# eagleproject.net
KiCad netlist of a schematic drawn in EAGLE
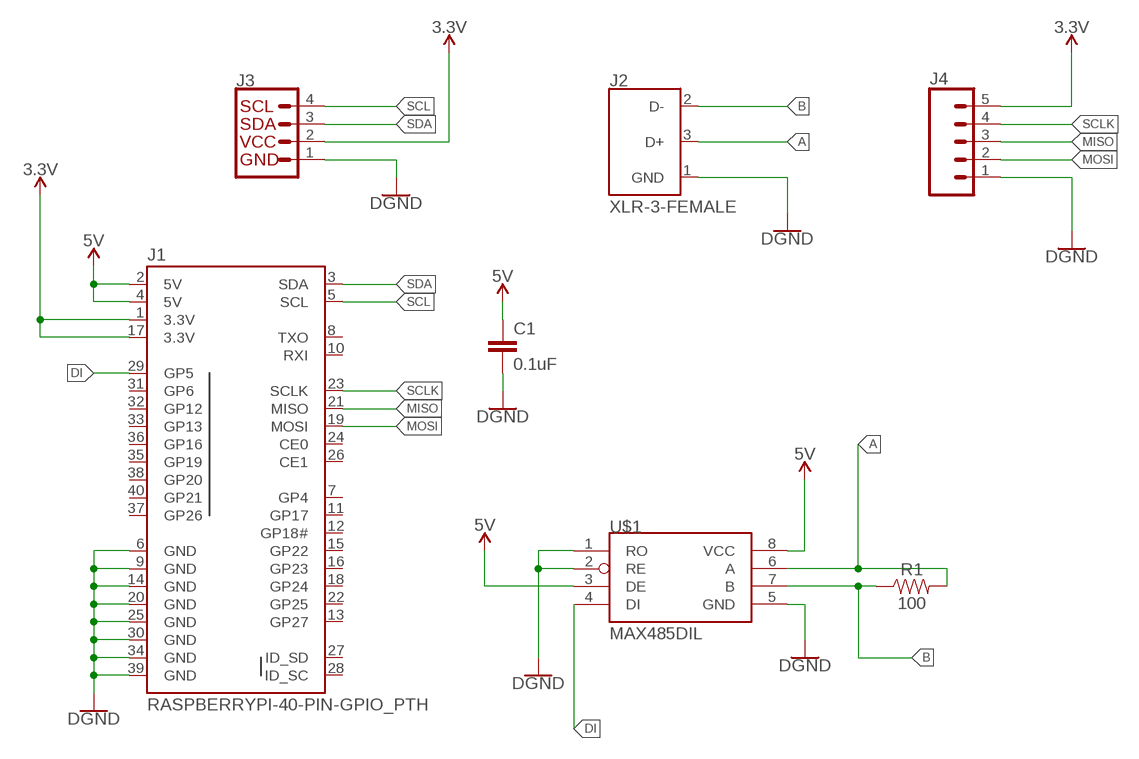
[diagram p0: schematic, sheet 1]

(export (version "E")
  (design (tool "Eeschema 10.0.6"))
  (components
    (comp (ref "C1")
      (value "0.1uF")
      (footprint "eagle-import:0603")
      (libsource (lib "eagle-import") (part "0.1UF-0603-25V-(+80/-20%)"))
    )
    (comp (ref "J1")
      (value "RASPBERRYPI-40-PIN-GPIO_PTH")
      (footprint "eagle-import:2X20_SHROUDED")
      (libsource (lib "eagle-import") (part "RASPBERRYPI-40-PIN-GPIO_PTH"))
    )
    (comp (ref "J2")
      (value "XLR-3-FEMALE")
      (footprint "eagle-import:XLR-3_FEMALE")
      (libsource (lib "eagle-import") (part "XLR-3-FEMALE"))
    )
    (comp (ref "J3")
      (value "I2C_STANDARD")
      (footprint "eagle-import:1X04")
      (libsource (lib "eagle-import") (part "I2C_STANDARD"))
    )
    (comp (ref "J4")
      (value "CONN_05")
      (footprint "eagle-import:1X05")
      (libsource (lib "eagle-import") (part "CONN_05"))
    )
    (comp (ref "R1")
      (value "100")
      (footprint "eagle-import:0603")
      (libsource (lib "eagle-import") (part "100OHM-0603-1/4W-5%"))
    )
    (comp (ref "U$1")
      (value "MAX485DIL")
      (footprint "eagle-import:DIL08")
      (libsource (lib "eagle-import") (part "MAX485DIL"))
    )
  )
  (nets
    (net (code "1") (name "3.3V") (class "Default")
      (node (ref "J1") (pin "1") (pinfunction "3.3V_1") (pintype "power_in"))
      (node (ref "J1") (pin "17") (pinfunction "3.3V_17") (pintype "power_in"))
      (node (ref "J3") (pin "2") (pinfunction "2_2") (pintype "power_in"))
      (node (ref "J4") (pin "5") (pinfunction "5_5") (pintype "passive"))
    )
    (net (code "2") (name "5V") (class "Default")
      (node (ref "C1") (pin "1") (pinfunction "1_1") (pintype "passive"))
      (node (ref "J1") (pin "2") (pinfunction "5V_2") (pintype "power_in"))
      (node (ref "J1") (pin "4") (pinfunction "5V_4") (pintype "power_in"))
      (node (ref "U$1") (pin "3") (pinfunction "DE_3") (pintype "bidirectional"))
      (node (ref "U$1") (pin "8") (pinfunction "VCC_8") (pintype "bidirectional"))
    )
    (net (code "3") (name "A") (class "Default")
      (node (ref "J2") (pin "3") (pinfunction "D+_3") (pintype "bidirectional"))
      (node (ref "R1") (pin "2") (pinfunction "2_2") (pintype "passive"))
      (node (ref "U$1") (pin "6") (pinfunction "A_6") (pintype "bidirectional"))
    )
    (net (code "4") (name "B") (class "Default")
      (node (ref "J2") (pin "2") (pinfunction "D-_2") (pintype "bidirectional"))
      (node (ref "R1") (pin "1") (pinfunction "1_1") (pintype "passive"))
      (node (ref "U$1") (pin "7") (pinfunction "B_7") (pintype "bidirectional"))
    )
    (net (code "5") (name "DGND") (class "Default")
      (node (ref "C1") (pin "2") (pinfunction "2_2") (pintype "passive"))
      (node (ref "J1") (pin "14") (pinfunction "GND_14") (pintype "power_in"))
      (node (ref "J1") (pin "20") (pinfunction "GND_20") (pintype "power_in"))
      (node (ref "J1") (pin "25") (pinfunction "GND_25") (pintype "power_in"))
      (node (ref "J1") (pin "30") (pinfunction "GND_30") (pintype "power_in"))
      (node (ref "J1") (pin "34") (pinfunction "GND_34") (pintype "power_in"))
      (node (ref "J1") (pin "39") (pinfunction "GND_39") (pintype "power_in"))
      (node (ref "J1") (pin "6") (pinfunction "GND_6") (pintype "power_in"))
      (node (ref "J1") (pin "9") (pinfunction "GND_9") (pintype "power_in"))
      (node (ref "J2") (pin "1") (pinfunction "GND_1") (pintype "bidirectional"))
      (node (ref "J3") (pin "1") (pinfunction "1_1") (pintype "power_in"))
      (node (ref "J4") (pin "1") (pinfunction "1_1") (pintype "passive"))
      (node (ref "U$1") (pin "1") (pinfunction "RO_1") (pintype "bidirectional"))
      (node (ref "U$1") (pin "2") (pinfunction "RE_2") (pintype "bidirectional"))
      (node (ref "U$1") (pin "5") (pinfunction "GND_5") (pintype "bidirectional"))
    )
    (net (code "6") (name "DI") (class "Default")
      (node (ref "J1") (pin "29") (pinfunction "GP5_29") (pintype "bidirectional"))
      (node (ref "U$1") (pin "4") (pinfunction "DI_4") (pintype "bidirectional"))
    )
    (net (code "7") (name "MISO") (class "Default")
      (node (ref "J1") (pin "21") (pinfunction "MISO_21") (pintype "input"))
      (node (ref "J4") (pin "3") (pinfunction "3_3") (pintype "passive"))
    )
    (net (code "8") (name "MOSI") (class "Default")
      (node (ref "J1") (pin "19") (pinfunction "MOSI_19") (pintype "output"))
      (node (ref "J4") (pin "2") (pinfunction "2_2") (pintype "passive"))
    )
    (net (code "9") (name "SCL") (class "Default")
      (node (ref "J1") (pin "5") (pinfunction "SCL_5") (pintype "bidirectional"))
      (node (ref "J3") (pin "4") (pinfunction "4_4") (pintype "passive"))
    )
    (net (code "10") (name "SCLK") (class "Default")
      (node (ref "J1") (pin "23") (pinfunction "SCLK_23") (pintype "output"))
      (node (ref "J4") (pin "4") (pinfunction "4_4") (pintype "passive"))
    )
    (net (code "11") (name "SDA") (class "Default")
      (node (ref "J1") (pin "3") (pinfunction "SDA_3") (pintype "bidirectional"))
      (node (ref "J3") (pin "3") (pinfunction "3_3") (pintype "passive"))
    )
    (net (code "12") (name "unconnected-(J1-CE0-Pad24)") (class "Default")
      (node (ref "J1") (pin "24") (pinfunction "CE0_24") (pintype "output"))
    )
    (net (code "13") (name "unconnected-(J1-CE1-Pad26)") (class "Default")
      (node (ref "J1") (pin "26") (pinfunction "CE1_26") (pintype "output"))
    )
    (net (code "14") (name "unconnected-(J1-GP4-Pad7)") (class "Default")
      (node (ref "J1") (pin "7") (pinfunction "GP4_7") (pintype "bidirectional"))
    )
    (net (code "15") (name "unconnected-(J1-GP6-Pad31)") (class "Default")
      (node (ref "J1") (pin "31") (pinfunction "GP6_31") (pintype "bidirectional"))
    )
    (net (code "16") (name "unconnected-(J1-GP12-Pad32)") (class "Default")
      (node (ref "J1") (pin "32") (pinfunction "GP12_32") (pintype "bidirectional"))
    )
    (net (code "17") (name "unconnected-(J1-GP13-Pad33)") (class "Default")
      (node (ref "J1") (pin "33") (pinfunction "GP13_33") (pintype "bidirectional"))
    )
    (net (code "18") (name "unconnected-(J1-GP16-Pad36)") (class "Default")
      (node (ref "J1") (pin "36") (pinfunction "GP16_36") (pintype "bidirectional"))
    )
    (net (code "19") (name "unconnected-(J1-GP17-Pad11)") (class "Default")
      (node (ref "J1") (pin "11") (pinfunction "GP17_11") (pintype "bidirectional"))
    )
    (net (code "20") (name "unconnected-(J1-GP18#-Pad12)") (class "Default")
      (node (ref "J1") (pin "12") (pinfunction "GP18#_12") (pintype "bidirectional"))
    )
    (net (code "21") (name "unconnected-(J1-GP19-Pad35)") (class "Default")
      (node (ref "J1") (pin "35") (pinfunction "GP19_35") (pintype "bidirectional"))
    )
    (net (code "22") (name "unconnected-(J1-GP20-Pad38)") (class "Default")
      (node (ref "J1") (pin "38") (pinfunction "GP20_38") (pintype "bidirectional"))
    )
    (net (code "23") (name "unconnected-(J1-GP21-Pad40)") (class "Default")
      (node (ref "J1") (pin "40") (pinfunction "GP21_40") (pintype "bidirectional"))
    )
    (net (code "24") (name "unconnected-(J1-GP22-Pad15)") (class "Default")
      (node (ref "J1") (pin "15") (pinfunction "GP22_15") (pintype "bidirectional"))
    )
    (net (code "25") (name "unconnected-(J1-GP23-Pad16)") (class "Default")
      (node (ref "J1") (pin "16") (pinfunction "GP23_16") (pintype "bidirectional"))
    )
    (net (code "26") (name "unconnected-(J1-GP24-Pad18)") (class "Default")
      (node (ref "J1") (pin "18") (pinfunction "GP24_18") (pintype "bidirectional"))
    )
    (net (code "27") (name "unconnected-(J1-GP25-Pad22)") (class "Default")
      (node (ref "J1") (pin "22") (pinfunction "GP25_22") (pintype "bidirectional"))
    )
    (net (code "28") (name "unconnected-(J1-GP26-Pad37)") (class "Default")
      (node (ref "J1") (pin "37") (pinfunction "GP26_37") (pintype "bidirectional"))
    )
    (net (code "29") (name "unconnected-(J1-GP27-Pad13)") (class "Default")
      (node (ref "J1") (pin "13") (pinfunction "GP27_13") (pintype "bidirectional"))
    )
    (net (code "30") (name "unconnected-(J1-ID_SC-Pad28)") (class "Default")
      (node (ref "J1") (pin "28") (pinfunction "ID_SC_28") (pintype "bidirectional"))
    )
    (net (code "31") (name "unconnected-(J1-ID_SD-Pad27)") (class "Default")
      (node (ref "J1") (pin "27") (pinfunction "ID_SD_27") (pintype "bidirectional"))
    )
    (net (code "32") (name "unconnected-(J1-RXI-Pad10)") (class "Default")
      (node (ref "J1") (pin "10") (pinfunction "RXI_10") (pintype "input"))
    )
    (net (code "33") (name "unconnected-(J1-TXO-Pad8)") (class "Default")
      (node (ref "J1") (pin "8") (pinfunction "TXO_8") (pintype "output"))
    )
  )
)
